# Zoetrope.net
KiCad netlist of a schematic drawn in EAGLE
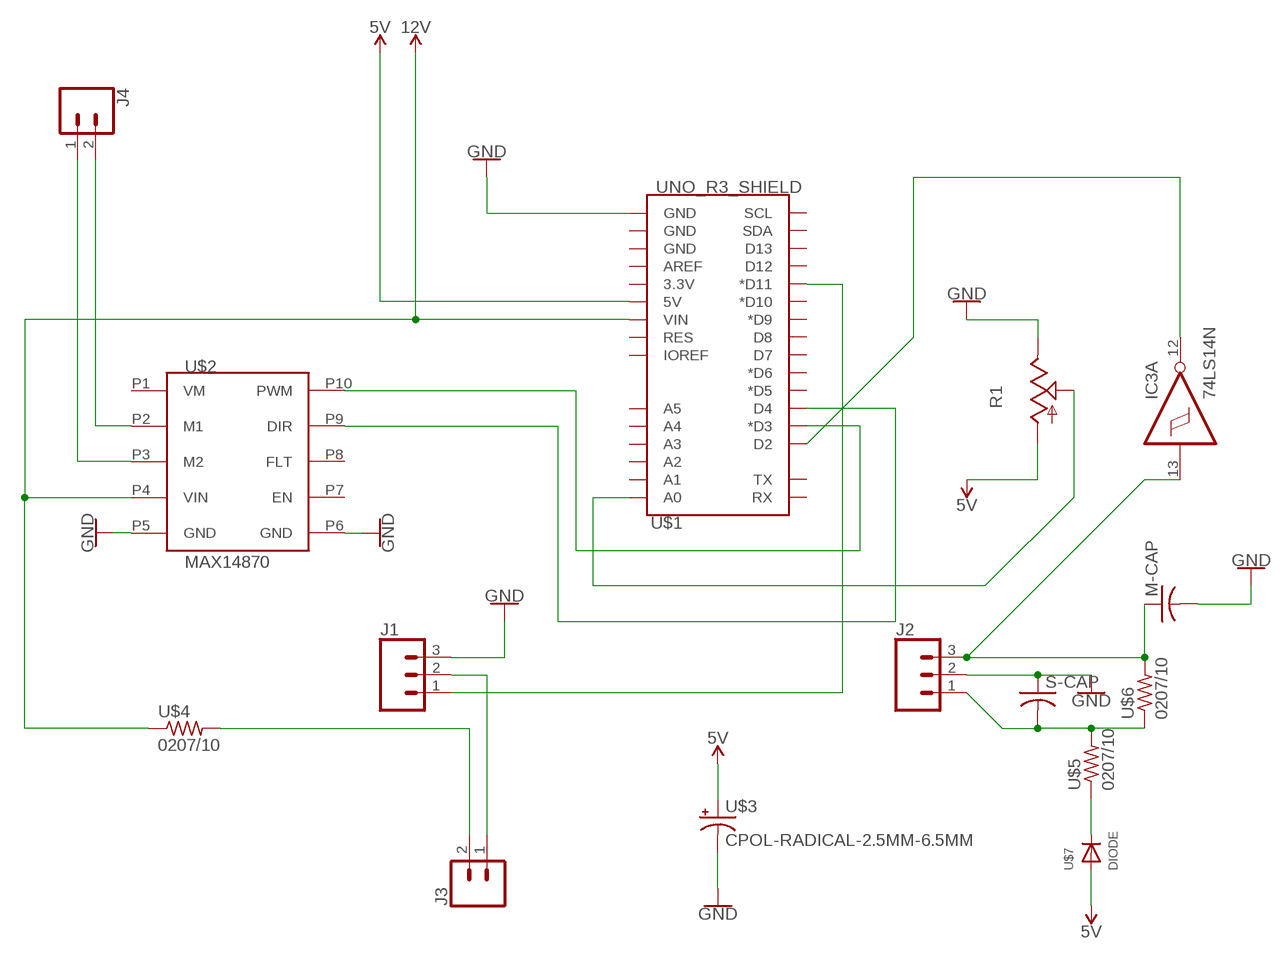
[diagram p0: schematic, sheet 1]

(export (version "E")
  (design (tool "Eeschema 10.0.6"))
  (components
    (comp (ref "IC3")
      (value "74LS14N")
      (footprint "eagle-import:DIL14")
      (libsource (lib "eagle-import") (part "7414NLS"))
    )
    (comp (ref "J1")
      (value "CONN_03LOCK_LONGPADS")
      (footprint "eagle-import:1X03_LOCK_LONGPADS")
      (libsource (lib "eagle-import") (part "CONN_03LOCK_LONGPADS"))
    )
    (comp (ref "J2")
      (value "CONN_03LOCK_LONGPADS")
      (footprint "eagle-import:1X03_LOCK_LONGPADS")
      (libsource (lib "eagle-import") (part "CONN_03LOCK_LONGPADS"))
    )
    (comp (ref "J3")
      (value "CONN_02LOCK_LONGPADS")
      (footprint "eagle-import:1X02_LOCK_LONGPADS")
      (libsource (lib "eagle-import") (part "CONN_02LOCK_LONGPADS"))
    )
    (comp (ref "J4")
      (value "CONN_02LOCK_LONGPADS")
      (footprint "eagle-import:1X02_LOCK_LONGPADS")
      (libsource (lib "eagle-import") (part "CONN_02LOCK_LONGPADS"))
    )
    (comp (ref "M-CAP")
      (value "C-US050-030X075")
      (footprint "eagle-import:C050-030X075")
      (libsource (lib "eagle-import") (part "C-US050-030X075"))
    )
    (comp (ref "R1")
      (value "TRIM_US-B25U")
      (footprint "eagle-import:B25U")
      (libsource (lib "eagle-import") (part "TRIM_US-B25U"))
    )
    (comp (ref "S-CAP")
      (value "C-US025-030X050")
      (footprint "eagle-import:C025-030X050")
      (libsource (lib "eagle-import") (part "C-US025-030X050"))
    )
    (comp (ref "U$1")
      (value "UNO_R3_SHIELD")
      (footprint "eagle-import:UNO_R3_SHIELD")
      (libsource (lib "eagle-import") (part "UNO_R3_SHIELD"))
    )
    (comp (ref "U$2")
      (value "MAX14870")
      (footprint "eagle-import:MAX14870")
      (libsource (lib "eagle-import") (part "MAX14870"))
    )
    (comp (ref "U$3")
      (value "CPOL-RADICAL-2.5MM-6.5MM")
      (footprint "eagle-import:CPOL-RADIAL-2.5MM-6.5MM")
      (libsource (lib "eagle-import") (part "CPOL-RADICAL-2.5MM-6.5MM"))
    )
    (comp (ref "U$4")
      (value "0207/10")
      (footprint "eagle-import:0207_10")
      (libsource (lib "eagle-import") (part "0207/10"))
    )
    (comp (ref "U$5")
      (value "0207/10")
      (footprint "eagle-import:0207_10")
      (libsource (lib "eagle-import") (part "0207/10"))
    )
    (comp (ref "U$6")
      (value "0207/10")
      (footprint "eagle-import:0207_10")
      (libsource (lib "eagle-import") (part "0207/10"))
    )
    (comp (ref "U$7")
      (value "DIODE")
      (footprint "eagle-import:DO-1N4148")
      (libsource (lib "eagle-import") (part "DIODE"))
    )
  )
  (nets
    (net (code "1") (name "5V") (class "Default")
      (node (ref "R1") (pin "A") (pinfunction "A_A") (pintype "passive"))
      (node (ref "U$1") (pin "5V") (pinfunction "5V_5V") (pintype "bidirectional"))
      (node (ref "U$3") (pin "1") (pinfunction "+_1") (pintype "passive"))
      (node (ref "U$7") (pin "A") (pinfunction "A_A") (pintype "passive"))
    )
    (net (code "2") (name "12V") (class "Default")
      (node (ref "U$1") (pin "VIN") (pinfunction "VIN_VIN") (pintype "bidirectional"))
      (node (ref "U$2") (pin "P4") (pinfunction "VIN_P4") (pintype "bidirectional"))
      (node (ref "U$4") (pin "1") (pinfunction "1_1") (pintype "passive"))
    )
    (net (code "3") (name "GND") (class "Default")
      (node (ref "J1") (pin "3") (pinfunction "3_3") (pintype "passive"))
      (node (ref "J2") (pin "2") (pinfunction "2_2") (pintype "passive"))
      (node (ref "M-CAP") (pin "2") (pinfunction "2_2") (pintype "passive"))
      (node (ref "R1") (pin "E") (pinfunction "E_E") (pintype "passive"))
      (node (ref "S-CAP") (pin "1") (pinfunction "1_1") (pintype "passive"))
      (node (ref "U$1") (pin "GND@0") (pinfunction "GND_GND@0") (pintype "bidirectional"))
      (node (ref "U$2") (pin "P5") (pinfunction "GND_P5") (pintype "bidirectional"))
      (node (ref "U$2") (pin "P6") (pinfunction "GND_P6") (pintype "bidirectional"))
      (node (ref "U$3") (pin "2") (pinfunction "-_2") (pintype "passive"))
    )
    (net (code "4") (name "Net-(IC3A-I)") (class "Default")
      (node (ref "IC3") (pin "13") (pinfunction "I_13") (pintype "input"))
      (node (ref "J2") (pin "3") (pinfunction "3_3") (pintype "passive"))
      (node (ref "M-CAP") (pin "1") (pinfunction "1_1") (pintype "passive"))
      (node (ref "U$6") (pin "2") (pinfunction "2_2") (pintype "passive"))
    )
    (net (code "5") (name "Net-(IC3A-O)") (class "Default")
      (node (ref "IC3") (pin "12") (pinfunction "O_12") (pintype "output"))
      (node (ref "U$1") (pin "D2") (pinfunction "D2_D2") (pintype "bidirectional"))
    )
    (net (code "6") (name "Net-(J1-Pad2)") (class "Default")
      (node (ref "J1") (pin "2") (pinfunction "2_2") (pintype "passive"))
      (node (ref "J3") (pin "1") (pinfunction "1_1") (pintype "passive"))
    )
    (net (code "7") (name "Net-(J2-Pad1)") (class "Default")
      (node (ref "J2") (pin "1") (pinfunction "1_1") (pintype "passive"))
      (node (ref "S-CAP") (pin "2") (pinfunction "2_2") (pintype "passive"))
      (node (ref "U$5") (pin "2") (pinfunction "2_2") (pintype "passive"))
      (node (ref "U$6") (pin "1") (pinfunction "1_1") (pintype "passive"))
    )
    (net (code "8") (name "Net-(J3-Pad2)") (class "Default")
      (node (ref "J3") (pin "2") (pinfunction "2_2") (pintype "passive"))
      (node (ref "U$4") (pin "2") (pinfunction "2_2") (pintype "passive"))
    )
    (net (code "9") (name "Net-(R1-PadS)") (class "Default")
      (node (ref "R1") (pin "S") (pinfunction "S_S") (pintype "passive"))
      (node (ref "U$1") (pin "A0") (pinfunction "A0_A0") (pintype "bidirectional"))
    )
    (net (code "10") (name "Net-(U$1-*D3)") (class "Default")
      (node (ref "U$1") (pin "D3") (pinfunction "*D3_D3") (pintype "bidirectional"))
      (node (ref "U$2") (pin "P10") (pinfunction "PWM_P10") (pintype "bidirectional"))
    )
    (net (code "11") (name "Net-(U$1-*D11)") (class "Default")
      (node (ref "J1") (pin "1") (pinfunction "1_1") (pintype "passive"))
      (node (ref "U$1") (pin "D11") (pinfunction "*D11_D11") (pintype "bidirectional"))
    )
    (net (code "12") (name "Net-(U$2-DIR)") (class "Default")
      (node (ref "U$1") (pin "D4") (pinfunction "D4_D4") (pintype "bidirectional"))
      (node (ref "U$2") (pin "P9") (pinfunction "DIR_P9") (pintype "bidirectional"))
    )
    (net (code "13") (name "Net-(U$2-M1)") (class "Default")
      (node (ref "J4") (pin "2") (pinfunction "2_2") (pintype "passive"))
      (node (ref "U$2") (pin "P2") (pinfunction "M1_P2") (pintype "bidirectional"))
    )
    (net (code "14") (name "Net-(U$2-M2)") (class "Default")
      (node (ref "J4") (pin "1") (pinfunction "1_1") (pintype "passive"))
      (node (ref "U$2") (pin "P3") (pinfunction "M2_P3") (pintype "bidirectional"))
    )
    (net (code "15") (name "Net-(U$5-Pad1)") (class "Default")
      (node (ref "U$5") (pin "1") (pinfunction "1_1") (pintype "passive"))
      (node (ref "U$7") (pin "C") (pinfunction "C_C") (pintype "passive"))
    )
    (net (code "16") (name "unconnected-(U$1-*D5-PadD5)") (class "Default")
      (node (ref "U$1") (pin "D5") (pinfunction "*D5_D5") (pintype "bidirectional"))
    )
    (net (code "17") (name "unconnected-(U$1-*D6-PadD6)") (class "Default")
      (node (ref "U$1") (pin "D6") (pinfunction "*D6_D6") (pintype "bidirectional"))
    )
    (net (code "18") (name "unconnected-(U$1-*D9-PadD9)") (class "Default")
      (node (ref "U$1") (pin "D9") (pinfunction "*D9_D9") (pintype "bidirectional"))
    )
    (net (code "19") (name "unconnected-(U$1-*D10-PadD10)") (class "Default")
      (node (ref "U$1") (pin "D10") (pinfunction "*D10_D10") (pintype "bidirectional"))
    )
    (net (code "20") (name "unconnected-(U$1-GND-PadGND@1)") (class "Default")
      (node (ref "U$1") (pin "GND@1") (pinfunction "GND_GND@1") (pintype "bidirectional"))
    )
    (net (code "21") (name "unconnected-(U$1-GND-PadGND@2)") (class "Default")
      (node (ref "U$1") (pin "GND@2") (pinfunction "GND_GND@2") (pintype "bidirectional"))
    )
    (net (code "22") (name "unconnected-(U$1-Pad3.3V)") (class "Default")
      (node (ref "U$1") (pin "3.3V") (pinfunction "3.3V_3.3V") (pintype "bidirectional"))
    )
    (net (code "23") (name "unconnected-(U$1-PadA1)") (class "Default")
      (node (ref "U$1") (pin "A1") (pinfunction "A1_A1") (pintype "bidirectional"))
    )
    (net (code "24") (name "unconnected-(U$1-PadA2)") (class "Default")
      (node (ref "U$1") (pin "A2") (pinfunction "A2_A2") (pintype "bidirectional"))
    )
    (net (code "25") (name "unconnected-(U$1-PadA3)") (class "Default")
      (node (ref "U$1") (pin "A3") (pinfunction "A3_A3") (pintype "bidirectional"))
    )
    (net (code "26") (name "unconnected-(U$1-PadA4)") (class "Default")
      (node (ref "U$1") (pin "A4") (pinfunction "A4_A4") (pintype "bidirectional"))
    )
    (net (code "27") (name "unconnected-(U$1-PadA5)") (class "Default")
      (node (ref "U$1") (pin "A5") (pinfunction "A5_A5") (pintype "bidirectional"))
    )
    (net (code "28") (name "unconnected-(U$1-PadAREF)") (class "Default")
      (node (ref "U$1") (pin "AREF") (pinfunction "AREF_AREF") (pintype "bidirectional"))
    )
    (net (code "29") (name "unconnected-(U$1-PadD7)") (class "Default")
      (node (ref "U$1") (pin "D7") (pinfunction "D7_D7") (pintype "bidirectional"))
    )
    (net (code "30") (name "unconnected-(U$1-PadD8)") (class "Default")
      (node (ref "U$1") (pin "D8") (pinfunction "D8_D8") (pintype "bidirectional"))
    )
    (net (code "31") (name "unconnected-(U$1-PadD12)") (class "Default")
      (node (ref "U$1") (pin "D12") (pinfunction "D12_D12") (pintype "bidirectional"))
    )
    (net (code "32") (name "unconnected-(U$1-PadD13)") (class "Default")
      (node (ref "U$1") (pin "D13") (pinfunction "D13_D13") (pintype "bidirectional"))
    )
    (net (code "33") (name "unconnected-(U$1-PadIOREF)") (class "Default")
      (node (ref "U$1") (pin "IOREF") (pinfunction "IOREF_IOREF") (pintype "bidirectional"))
    )
    (net (code "34") (name "unconnected-(U$1-PadRES)") (class "Default")
      (node (ref "U$1") (pin "RES") (pinfunction "RES_RES") (pintype "bidirectional"))
    )
    (net (code "35") (name "unconnected-(U$1-PadRX)") (class "Default")
      (node (ref "U$1") (pin "RX") (pinfunction "RX_RX") (pintype "bidirectional"))
    )
    (net (code "36") (name "unconnected-(U$1-PadSCL)") (class "Default")
      (node (ref "U$1") (pin "SCL") (pinfunction "SCL_SCL") (pintype "bidirectional"))
    )
    (net (code "37") (name "unconnected-(U$1-PadSDA)") (class "Default")
      (node (ref "U$1") (pin "SDA") (pinfunction "SDA_SDA") (pintype "bidirectional"))
    )
    (net (code "38") (name "unconnected-(U$1-PadTX)") (class "Default")
      (node (ref "U$1") (pin "TX") (pinfunction "TX_TX") (pintype "bidirectional"))
    )
    (net (code "39") (name "unconnected-(U$2-EN-PadP7)") (class "Default")
      (node (ref "U$2") (pin "P7") (pinfunction "EN_P7") (pintype "bidirectional"))
    )
    (net (code "40") (name "unconnected-(U$2-FLT-PadP8)") (class "Default")
      (node (ref "U$2") (pin "P8") (pinfunction "FLT_P8") (pintype "bidirectional"))
    )
    (net (code "41") (name "unconnected-(U$2-VM-PadP1)") (class "Default")
      (node (ref "U$2") (pin "P1") (pinfunction "VM_P1") (pintype "bidirectional"))
    )
  )
)
